# Wrist.net
KiCad netlist of a schematic drawn in Altium Designer
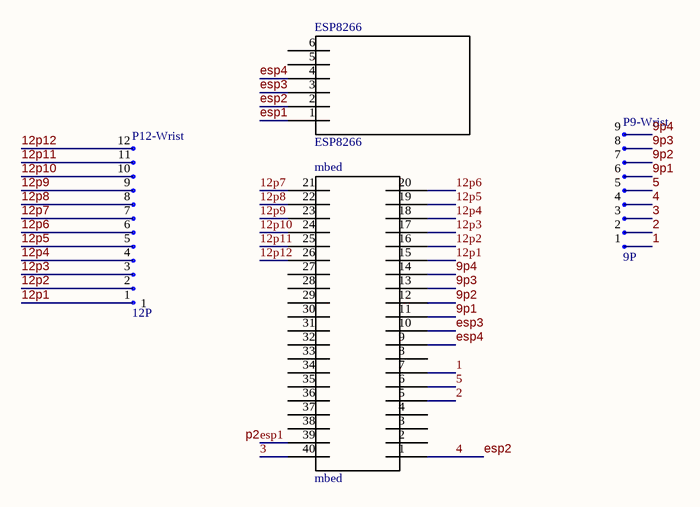
[diagram p0: Wrist.SchDoc]

(export (version "E")
  (design (tool "Eeschema 10.0.6"))
  (components
    (comp (ref "ESP8266") (value "ESP8266") (footprint "ESP8266") (libsource (lib "IMU") (part "ESP8266")))
    (comp (ref "mbed") (value "mbed") (footprint "Mbed") (libsource (lib "IMU") (part "mbed")))
    (comp (ref "P9-Wrist") (value "9P") (footprint "9p") (libsource (lib "IMU") (part "9P")))
    (comp (ref "P12-Wrist") (value "12P") (footprint "12P") (libsource (lib "IMU") (part "12P")))
  )
  (nets
    (net (code "1") (name "/1") (class "Default")
      (node (ref "P9-Wrist") (pin "1") (pinfunction "1_1") (pintype "passive"))
      (node (ref "mbed") (pin "7") (pinfunction "7_7") (pintype "passive"))
    )
    (net (code "2") (name "/2") (class "Default")
      (node (ref "P9-Wrist") (pin "2") (pinfunction "2_2") (pintype "passive"))
      (node (ref "mbed") (pin "5") (pinfunction "5_5") (pintype "passive"))
    )
    (net (code "3") (name "/3") (class "Default")
      (node (ref "P9-Wrist") (pin "3") (pinfunction "3_3") (pintype "passive"))
      (node (ref "mbed") (pin "40") (pinfunction "40_40") (pintype "passive"))
    )
    (net (code "4") (name "/4") (class "Default")
      (node (ref "ESP8266") (pin "2") (pinfunction "2_2") (pintype "passive"))
      (node (ref "P9-Wrist") (pin "4") (pinfunction "4_4") (pintype "passive"))
      (node (ref "mbed") (pin "1") (pinfunction "1_1") (pintype "passive"))
    )
    (net (code "5") (name "/5") (class "Default")
      (node (ref "P9-Wrist") (pin "5") (pinfunction "5_5") (pintype "passive"))
      (node (ref "mbed") (pin "6") (pinfunction "6_6") (pintype "passive"))
    )
    (net (code "6") (name "/9p1") (class "Default")
      (node (ref "P9-Wrist") (pin "6") (pinfunction "6_6") (pintype "passive"))
      (node (ref "mbed") (pin "11") (pinfunction "11_11") (pintype "passive"))
    )
    (net (code "7") (name "/9p2") (class "Default")
      (node (ref "P9-Wrist") (pin "7") (pinfunction "7_7") (pintype "passive"))
      (node (ref "mbed") (pin "12") (pinfunction "12_12") (pintype "passive"))
    )
    (net (code "8") (name "/9p3") (class "Default")
      (node (ref "P9-Wrist") (pin "8") (pinfunction "8_8") (pintype "passive"))
      (node (ref "mbed") (pin "13") (pinfunction "13_13") (pintype "passive"))
    )
    (net (code "9") (name "/9p4") (class "Default")
      (node (ref "P9-Wrist") (pin "9") (pinfunction "9_9") (pintype "passive"))
      (node (ref "mbed") (pin "14") (pinfunction "14_14") (pintype "passive"))
    )
    (net (code "10") (name "/12p1") (class "Default")
      (node (ref "P12-Wrist") (pin "1") (pinfunction "1_1") (pintype "passive"))
      (node (ref "mbed") (pin "15") (pinfunction "15_15") (pintype "passive"))
    )
    (net (code "11") (name "/12p2") (class "Default")
      (node (ref "P12-Wrist") (pin "2") (pinfunction "2_2") (pintype "passive"))
      (node (ref "mbed") (pin "16") (pinfunction "16_16") (pintype "passive"))
    )
    (net (code "12") (name "/12p3") (class "Default")
      (node (ref "P12-Wrist") (pin "3") (pinfunction "3_3") (pintype "passive"))
      (node (ref "mbed") (pin "17") (pinfunction "17_17") (pintype "passive"))
    )
    (net (code "13") (name "/12p4") (class "Default")
      (node (ref "P12-Wrist") (pin "4") (pinfunction "4_4") (pintype "passive"))
      (node (ref "mbed") (pin "18") (pinfunction "18_18") (pintype "passive"))
    )
    (net (code "14") (name "/12p5") (class "Default")
      (node (ref "P12-Wrist") (pin "5") (pinfunction "5_5") (pintype "passive"))
      (node (ref "mbed") (pin "19") (pinfunction "19_19") (pintype "passive"))
    )
    (net (code "15") (name "/12p6") (class "Default")
      (node (ref "P12-Wrist") (pin "6") (pinfunction "6_6") (pintype "passive"))
      (node (ref "mbed") (pin "20") (pinfunction "20_20") (pintype "passive"))
    )
    (net (code "16") (name "/12p7") (class "Default")
      (node (ref "P12-Wrist") (pin "7") (pinfunction "7_7") (pintype "passive"))
      (node (ref "mbed") (pin "21") (pinfunction "21_21") (pintype "passive"))
    )
    (net (code "17") (name "/12p8") (class "Default")
      (node (ref "P12-Wrist") (pin "8") (pinfunction "8_8") (pintype "passive"))
      (node (ref "mbed") (pin "22") (pinfunction "22_22") (pintype "passive"))
    )
    (net (code "18") (name "/12p9") (class "Default")
      (node (ref "P12-Wrist") (pin "9") (pinfunction "9_9") (pintype "passive"))
      (node (ref "mbed") (pin "23") (pinfunction "23_23") (pintype "passive"))
    )
    (net (code "19") (name "/12p10") (class "Default")
      (node (ref "P12-Wrist") (pin "10") (pinfunction "10_10") (pintype "passive"))
      (node (ref "mbed") (pin "24") (pinfunction "24_24") (pintype "passive"))
    )
    (net (code "20") (name "/12p11") (class "Default")
      (node (ref "P12-Wrist") (pin "11") (pinfunction "11_11") (pintype "passive"))
      (node (ref "mbed") (pin "25") (pinfunction "25_25") (pintype "passive"))
    )
    (net (code "21") (name "/12p12") (class "Default")
      (node (ref "P12-Wrist") (pin "12") (pinfunction "12_12") (pintype "passive"))
      (node (ref "mbed") (pin "26") (pinfunction "26_26") (pintype "passive"))
    )
    (net (code "22") (name "/esp1") (class "Default")
      (node (ref "ESP8266") (pin "1") (pinfunction "1_1") (pintype "passive"))
      (node (ref "mbed") (pin "39") (pinfunction "39_39") (pintype "passive"))
    )
    (net (code "23") (name "/esp3") (class "Default")
      (node (ref "ESP8266") (pin "3") (pinfunction "3_3") (pintype "passive"))
      (node (ref "mbed") (pin "10") (pinfunction "10_10") (pintype "passive"))
    )
    (net (code "24") (name "/esp4") (class "Default")
      (node (ref "ESP8266") (pin "4") (pinfunction "4_4") (pintype "passive"))
      (node (ref "mbed") (pin "9") (pinfunction "9_9") (pintype "passive"))
    )
    (net (code "26") (name "unconnected-(ESP8266-Pad5)") (class "Default")
      (node (ref "ESP8266") (pin "5") (pinfunction "5_5") (pintype "passive"))
    )
    (net (code "27") (name "unconnected-(ESP8266-Pad6)") (class "Default")
      (node (ref "ESP8266") (pin "6") (pinfunction "6_6") (pintype "passive"))
    )
    (net (code "28") (name "unconnected-(mbed-Pad2)") (class "Default")
      (node (ref "mbed") (pin "2") (pinfunction "2_2") (pintype "passive"))
    )
    (net (code "29") (name "unconnected-(mbed-Pad3)") (class "Default")
      (node (ref "mbed") (pin "3") (pinfunction "3_3") (pintype "passive"))
    )
    (net (code "30") (name "unconnected-(mbed-Pad4)") (class "Default")
      (node (ref "mbed") (pin "4") (pinfunction "4_4") (pintype "passive"))
    )
    (net (code "31") (name "unconnected-(mbed-Pad8)") (class "Default")
      (node (ref "mbed") (pin "8") (pinfunction "8_8") (pintype "passive"))
    )
    (net (code "32") (name "unconnected-(mbed-Pad27)") (class "Default")
      (node (ref "mbed") (pin "27") (pinfunction "27_27") (pintype "passive"))
    )
    (net (code "33") (name "unconnected-(mbed-Pad28)") (class "Default")
      (node (ref "mbed") (pin "28") (pinfunction "28_28") (pintype "passive"))
    )
    (net (code "34") (name "unconnected-(mbed-Pad29)") (class "Default")
      (node (ref "mbed") (pin "29") (pinfunction "29_29") (pintype "passive"))
    )
    (net (code "35") (name "unconnected-(mbed-Pad30)") (class "Default")
      (node (ref "mbed") (pin "30") (pinfunction "30_30") (pintype "passive"))
    )
    (net (code "36") (name "unconnected-(mbed-Pad31)") (class "Default")
      (node (ref "mbed") (pin "31") (pinfunction "31_31") (pintype "passive"))
    )
    (net (code "37") (name "unconnected-(mbed-Pad32)") (class "Default")
      (node (ref "mbed") (pin "32") (pinfunction "32_32") (pintype "passive"))
    )
    (net (code "38") (name "unconnected-(mbed-Pad33)") (class "Default")
      (node (ref "mbed") (pin "33") (pinfunction "33_33") (pintype "passive"))
    )
    (net (code "39") (name "unconnected-(mbed-Pad34)") (class "Default")
      (node (ref "mbed") (pin "34") (pinfunction "34_34") (pintype "passive"))
    )
    (net (code "40") (name "unconnected-(mbed-Pad35)") (class "Default")
      (node (ref "mbed") (pin "35") (pinfunction "35_35") (pintype "passive"))
    )
    (net (code "41") (name "unconnected-(mbed-Pad36)") (class "Default")
      (node (ref "mbed") (pin "36") (pinfunction "36_36") (pintype "passive"))
    )
    (net (code "42") (name "unconnected-(mbed-Pad37)") (class "Default")
      (node (ref "mbed") (pin "37") (pinfunction "37_37") (pintype "passive"))
    )
    (net (code "43") (name "unconnected-(mbed-Pad38)") (class "Default")
      (node (ref "mbed") (pin "38") (pinfunction "38_38") (pintype "passive"))
    )
  )
)
